# 02_battery_powered_v0001.net
KiCad netlist of a schematic drawn in EAGLE
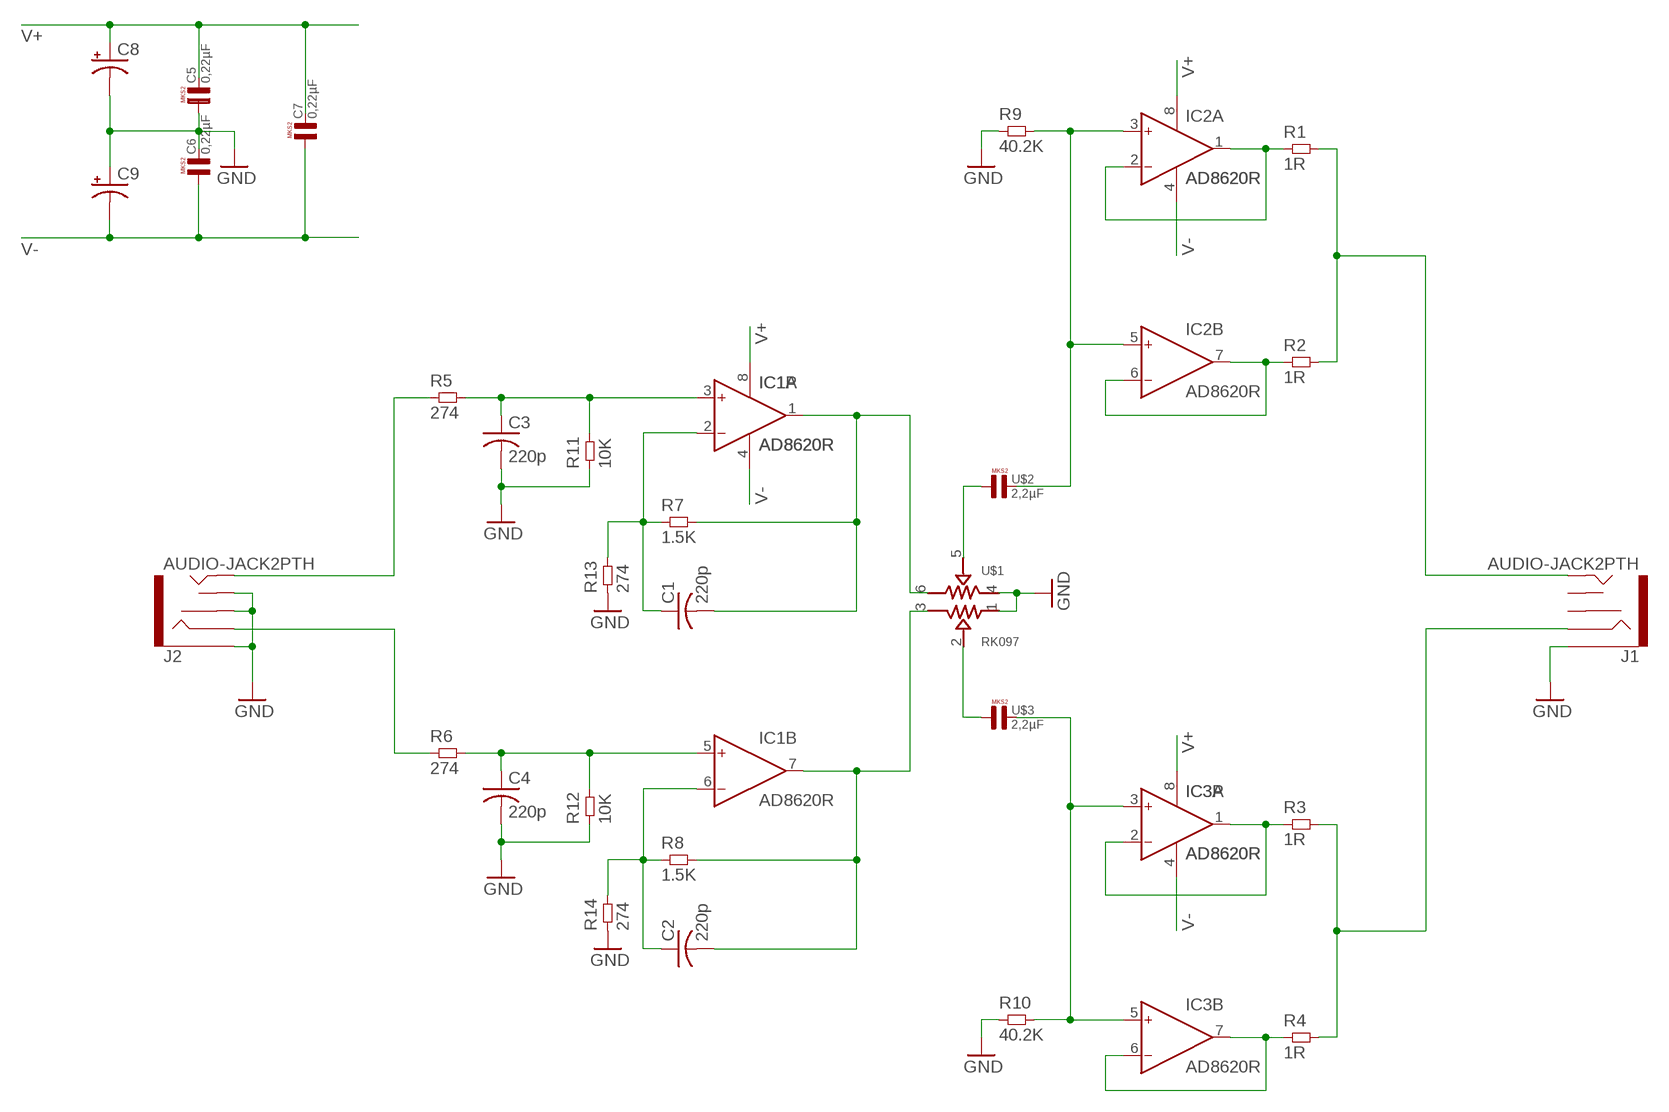
[diagram p0: schematic, sheet 1]

(export (version "E")
  (design (tool "Eeschema 10.0.6"))
  (components
    (comp (ref "C1")
      (value "220p")
      (footprint "eagle-import:C025-050X050")
      (libsource (lib "eagle-import") (part "C-US025-050X050"))
    )
    (comp (ref "C2")
      (value "220p")
      (footprint "eagle-import:C025-050X050")
      (libsource (lib "eagle-import") (part "C-US025-050X050"))
    )
    (comp (ref "C3")
      (value "220p")
      (footprint "eagle-import:C025-050X050")
      (libsource (lib "eagle-import") (part "C-US025-050X050"))
    )
    (comp (ref "C4")
      (value "220p")
      (footprint "eagle-import:C025-050X050")
      (libsource (lib "eagle-import") (part "C-US025-050X050"))
    )
    (comp (ref "C5")
      (value "0,22µF")
      (footprint "eagle-import:R5B3")
      (libsource (lib "eagle-import") (part "0,22µF"))
    )
    (comp (ref "C6")
      (value "0,22µF")
      (footprint "eagle-import:R5B3")
      (libsource (lib "eagle-import") (part "0,22µF"))
    )
    (comp (ref "C7")
      (value "0,22µF")
      (footprint "eagle-import:R5B3")
      (libsource (lib "eagle-import") (part "0,22µF"))
    )
    (comp (ref "C8")
      (value "CPOL-US150CLZ-1010")
      (footprint "eagle-import:150CLZ-1010")
      (libsource (lib "eagle-import") (part "CPOL-US150CLZ-1010"))
    )
    (comp (ref "C9")
      (value "CPOL-US150CLZ-1010")
      (footprint "eagle-import:150CLZ-1010")
      (libsource (lib "eagle-import") (part "CPOL-US150CLZ-1010"))
    )
    (comp (ref "IC1")
      (value "AD8620R")
      (footprint "eagle-import:SO8")
      (fields (field (name "MF") "ALTERA CORPORATION") (field (name "MPN") "AD8620ARZ"))
      (libsource (lib "eagle-import") (part "AD8620R"))
    )
    (comp (ref "IC2")
      (value "AD8620R")
      (footprint "eagle-import:SO8")
      (fields (field (name "MF") "ALTERA CORPORATION") (field (name "MPN") "AD8620ARZ"))
      (libsource (lib "eagle-import") (part "AD8620R"))
    )
    (comp (ref "IC3")
      (value "AD8620R")
      (footprint "eagle-import:SO8")
      (fields (field (name "MF") "ALTERA CORPORATION") (field (name "MPN") "AD8620ARZ"))
      (libsource (lib "eagle-import") (part "AD8620R"))
    )
    (comp (ref "J1")
      (value "AUDIO-JACK2PTH")
      (footprint "eagle-import:AUDIO-JACK")
      (libsource (lib "eagle-import") (part "AUDIO-JACK2PTH"))
    )
    (comp (ref "J2")
      (value "AUDIO-JACK2PTH")
      (footprint "eagle-import:AUDIO-JACK")
      (libsource (lib "eagle-import") (part "AUDIO-JACK2PTH"))
    )
    (comp (ref "R1")
      (value "1R")
      (footprint "eagle-import:1206L3")
      (libsource (lib "eagle-import") (part "RES1206L3"))
    )
    (comp (ref "R2")
      (value "1R")
      (footprint "eagle-import:1206L3")
      (libsource (lib "eagle-import") (part "RES1206L3"))
    )
    (comp (ref "R3")
      (value "1R")
      (footprint "eagle-import:1206L3")
      (libsource (lib "eagle-import") (part "RES1206L3"))
    )
    (comp (ref "R4")
      (value "1R")
      (footprint "eagle-import:1206L3")
      (libsource (lib "eagle-import") (part "RES1206L3"))
    )
    (comp (ref "R5")
      (value "274")
      (footprint "eagle-import:0603L3")
      (libsource (lib "eagle-import") (part "RES0603L3"))
    )
    (comp (ref "R6")
      (value "274")
      (footprint "eagle-import:0603L3")
      (libsource (lib "eagle-import") (part "RES0603L3"))
    )
    (comp (ref "R7")
      (value "1.5K")
      (footprint "eagle-import:0603L3")
      (libsource (lib "eagle-import") (part "RES0603L3"))
    )
    (comp (ref "R8")
      (value "1.5K")
      (footprint "eagle-import:0603L3")
      (libsource (lib "eagle-import") (part "RES0603L3"))
    )
    (comp (ref "R9")
      (value "40.2K")
      (footprint "eagle-import:0603L3")
      (libsource (lib "eagle-import") (part "RES0603L3"))
    )
    (comp (ref "R10")
      (value "40.2K")
      (footprint "eagle-import:0603L3")
      (libsource (lib "eagle-import") (part "RES0603L3"))
    )
    (comp (ref "R11")
      (value "10K")
      (footprint "eagle-import:0603L3")
      (libsource (lib "eagle-import") (part "RES0603L3"))
    )
    (comp (ref "R12")
      (value "10K")
      (footprint "eagle-import:0603L3")
      (libsource (lib "eagle-import") (part "RES0603L3"))
    )
    (comp (ref "R13")
      (value "274")
      (footprint "eagle-import:0603L3")
      (libsource (lib "eagle-import") (part "RES0603L3"))
    )
    (comp (ref "R14")
      (value "274")
      (footprint "eagle-import:0603L3")
      (libsource (lib "eagle-import") (part "RES0603L3"))
    )
    (comp (ref "U$1")
      (value "RK097")
      (footprint "eagle-import:RK097")
      (libsource (lib "eagle-import") (part "RK097"))
    )
    (comp (ref "U$2")
      (value "2,2µF")
      (footprint "eagle-import:R5B7K2")
      (libsource (lib "eagle-import") (part "2,2µF"))
    )
    (comp (ref "U$3")
      (value "2,2µF")
      (footprint "eagle-import:R5B7K2")
      (libsource (lib "eagle-import") (part "2,2µF"))
    )
  )
  (nets
    (net (code "1") (name "/V+") (class "Default")
      (node (ref "C5") (pin "2") (pinfunction "2_2") (pintype "passive"))
      (node (ref "C7") (pin "2") (pinfunction "2_2") (pintype "passive"))
      (node (ref "C8") (pin "+") (pinfunction "+_+") (pintype "passive"))
      (node (ref "IC1") (pin "8") (pinfunction "V+_8") (pintype "power_in"))
      (node (ref "IC2") (pin "8") (pinfunction "V+_8") (pintype "power_in"))
      (node (ref "IC3") (pin "8") (pinfunction "V+_8") (pintype "power_in"))
    )
    (net (code "2") (name "/V-") (class "Default")
      (node (ref "C6") (pin "1") (pinfunction "1_1") (pintype "passive"))
      (node (ref "C7") (pin "1") (pinfunction "1_1") (pintype "passive"))
      (node (ref "C9") (pin "-") (pinfunction "-_-") (pintype "passive"))
      (node (ref "IC1") (pin "4") (pinfunction "V-_4") (pintype "power_in"))
      (node (ref "IC2") (pin "4") (pinfunction "V-_4") (pintype "power_in"))
      (node (ref "IC3") (pin "4") (pinfunction "V-_4") (pintype "power_in"))
    )
    (net (code "3") (name "GND") (class "Default")
      (node (ref "C3") (pin "2") (pinfunction "2_2") (pintype "passive"))
      (node (ref "C4") (pin "2") (pinfunction "2_2") (pintype "passive"))
      (node (ref "C5") (pin "1") (pinfunction "1_1") (pintype "passive"))
      (node (ref "C6") (pin "2") (pinfunction "2_2") (pintype "passive"))
      (node (ref "C8") (pin "-") (pinfunction "-_-") (pintype "passive"))
      (node (ref "C9") (pin "+") (pinfunction "+_+") (pintype "passive"))
      (node (ref "J1") (pin "SLEEVE") (pinfunction "SLEEVE_SLEEVE") (pintype "bidirectional"))
      (node (ref "J2") (pin "RSH") (pinfunction "RSH_RSH") (pintype "bidirectional"))
      (node (ref "J2") (pin "SLEEVE") (pinfunction "SLEEVE_SLEEVE") (pintype "bidirectional"))
      (node (ref "J2") (pin "TSH") (pinfunction "TSH_TSH") (pintype "bidirectional"))
      (node (ref "R10") (pin "P$1") (pinfunction "1_P$1") (pintype "bidirectional"))
      (node (ref "R11") (pin "P$1") (pinfunction "1_P$1") (pintype "bidirectional"))
      (node (ref "R12") (pin "P$1") (pinfunction "1_P$1") (pintype "bidirectional"))
      (node (ref "R13") (pin "P$1") (pinfunction "1_P$1") (pintype "bidirectional"))
      (node (ref "R14") (pin "P$1") (pinfunction "1_P$1") (pintype "bidirectional"))
      (node (ref "R9") (pin "P$1") (pinfunction "1_P$1") (pintype "bidirectional"))
      (node (ref "U$1") (pin "1") (pinfunction "1_1") (pintype "bidirectional"))
      (node (ref "U$1") (pin "4") (pinfunction "4_4") (pintype "bidirectional"))
    )
    (net (code "4") (name "Net-(IC1A-IN+)") (class "Default")
      (node (ref "C3") (pin "1") (pinfunction "1_1") (pintype "passive"))
      (node (ref "IC1") (pin "3") (pinfunction "IN+_3") (pintype "input"))
      (node (ref "R11") (pin "P$2") (pinfunction "2_P$2") (pintype "bidirectional"))
      (node (ref "R5") (pin "P$2") (pinfunction "2_P$2") (pintype "bidirectional"))
    )
    (net (code "5") (name "Net-(IC1A-IN-)") (class "Default")
      (node (ref "C1") (pin "1") (pinfunction "1_1") (pintype "passive"))
      (node (ref "IC1") (pin "2") (pinfunction "IN-_2") (pintype "input"))
      (node (ref "R13") (pin "P$2") (pinfunction "2_P$2") (pintype "bidirectional"))
      (node (ref "R7") (pin "P$1") (pinfunction "1_P$1") (pintype "bidirectional"))
    )
    (net (code "6") (name "Net-(IC1A-OUT)") (class "Default")
      (node (ref "C1") (pin "2") (pinfunction "2_2") (pintype "passive"))
      (node (ref "IC1") (pin "1") (pinfunction "OUT_1") (pintype "output"))
      (node (ref "R7") (pin "P$2") (pinfunction "2_P$2") (pintype "bidirectional"))
      (node (ref "U$1") (pin "6") (pinfunction "6_6") (pintype "bidirectional"))
    )
    (net (code "7") (name "Net-(IC1B-IN+)") (class "Default")
      (node (ref "C4") (pin "1") (pinfunction "1_1") (pintype "passive"))
      (node (ref "IC1") (pin "5") (pinfunction "IN+_5") (pintype "input"))
      (node (ref "R12") (pin "P$2") (pinfunction "2_P$2") (pintype "bidirectional"))
      (node (ref "R6") (pin "P$2") (pinfunction "2_P$2") (pintype "bidirectional"))
    )
    (net (code "8") (name "Net-(IC1B-IN-)") (class "Default")
      (node (ref "C2") (pin "1") (pinfunction "1_1") (pintype "passive"))
      (node (ref "IC1") (pin "6") (pinfunction "IN-_6") (pintype "input"))
      (node (ref "R14") (pin "P$2") (pinfunction "2_P$2") (pintype "bidirectional"))
      (node (ref "R8") (pin "P$1") (pinfunction "1_P$1") (pintype "bidirectional"))
    )
    (net (code "9") (name "Net-(IC1B-OUT)") (class "Default")
      (node (ref "C2") (pin "2") (pinfunction "2_2") (pintype "passive"))
      (node (ref "IC1") (pin "7") (pinfunction "OUT_7") (pintype "output"))
      (node (ref "R8") (pin "P$2") (pinfunction "2_P$2") (pintype "bidirectional"))
      (node (ref "U$1") (pin "3") (pinfunction "3_3") (pintype "bidirectional"))
    )
    (net (code "10") (name "Net-(IC2A-IN+)") (class "Default")
      (node (ref "IC2") (pin "3") (pinfunction "IN+_3") (pintype "input"))
      (node (ref "IC2") (pin "5") (pinfunction "IN+_5") (pintype "input"))
      (node (ref "R9") (pin "P$2") (pinfunction "2_P$2") (pintype "bidirectional"))
      (node (ref "U$2") (pin "2") (pinfunction "2_2") (pintype "passive"))
    )
    (net (code "11") (name "Net-(IC2A-IN-)") (class "Default")
      (node (ref "IC2") (pin "1") (pinfunction "OUT_1") (pintype "output"))
      (node (ref "IC2") (pin "2") (pinfunction "IN-_2") (pintype "input"))
      (node (ref "R1") (pin "1") (pinfunction "1_1") (pintype "bidirectional"))
    )
    (net (code "12") (name "Net-(IC2B-IN-)") (class "Default")
      (node (ref "IC2") (pin "6") (pinfunction "IN-_6") (pintype "input"))
      (node (ref "IC2") (pin "7") (pinfunction "OUT_7") (pintype "output"))
      (node (ref "R2") (pin "1") (pinfunction "1_1") (pintype "bidirectional"))
    )
    (net (code "13") (name "Net-(IC3A-IN+)") (class "Default")
      (node (ref "IC3") (pin "3") (pinfunction "IN+_3") (pintype "input"))
      (node (ref "IC3") (pin "5") (pinfunction "IN+_5") (pintype "input"))
      (node (ref "R10") (pin "P$2") (pinfunction "2_P$2") (pintype "bidirectional"))
      (node (ref "U$3") (pin "2") (pinfunction "2_2") (pintype "passive"))
    )
    (net (code "14") (name "Net-(IC3A-IN-)") (class "Default")
      (node (ref "IC3") (pin "1") (pinfunction "OUT_1") (pintype "output"))
      (node (ref "IC3") (pin "2") (pinfunction "IN-_2") (pintype "input"))
      (node (ref "R3") (pin "1") (pinfunction "1_1") (pintype "bidirectional"))
    )
    (net (code "15") (name "Net-(IC3B-IN-)") (class "Default")
      (node (ref "IC3") (pin "6") (pinfunction "IN-_6") (pintype "input"))
      (node (ref "IC3") (pin "7") (pinfunction "OUT_7") (pintype "output"))
      (node (ref "R4") (pin "1") (pinfunction "1_1") (pintype "bidirectional"))
    )
    (net (code "16") (name "Net-(J1-PadRING)") (class "Default")
      (node (ref "J1") (pin "RING") (pinfunction "RING_RING") (pintype "bidirectional"))
      (node (ref "R3") (pin "2") (pinfunction "2_2") (pintype "bidirectional"))
      (node (ref "R4") (pin "2") (pinfunction "2_2") (pintype "bidirectional"))
    )
    (net (code "17") (name "Net-(J1-PadTIP)") (class "Default")
      (node (ref "J1") (pin "TIP") (pinfunction "TIP_TIP") (pintype "bidirectional"))
      (node (ref "R1") (pin "2") (pinfunction "2_2") (pintype "bidirectional"))
      (node (ref "R2") (pin "2") (pinfunction "2_2") (pintype "bidirectional"))
    )
    (net (code "18") (name "Net-(R5-1)") (class "Default")
      (node (ref "J2") (pin "TIP") (pinfunction "TIP_TIP") (pintype "bidirectional"))
      (node (ref "R5") (pin "P$1") (pinfunction "1_P$1") (pintype "bidirectional"))
    )
    (net (code "19") (name "Net-(R6-1)") (class "Default")
      (node (ref "J2") (pin "RING") (pinfunction "RING_RING") (pintype "bidirectional"))
      (node (ref "R6") (pin "P$1") (pinfunction "1_P$1") (pintype "bidirectional"))
    )
    (net (code "20") (name "Net-(U$1-Pad2)") (class "Default")
      (node (ref "U$1") (pin "2") (pinfunction "2_2") (pintype "bidirectional"))
      (node (ref "U$3") (pin "1") (pinfunction "1_1") (pintype "passive"))
    )
    (net (code "21") (name "Net-(U$1-Pad5)") (class "Default")
      (node (ref "U$1") (pin "5") (pinfunction "5_5") (pintype "bidirectional"))
      (node (ref "U$2") (pin "1") (pinfunction "1_1") (pintype "passive"))
    )
    (net (code "22") (name "unconnected-(J1-PadRSH)") (class "Default")
      (node (ref "J1") (pin "RSH") (pinfunction "RSH_RSH") (pintype "bidirectional"))
    )
    (net (code "23") (name "unconnected-(J1-PadTSH)") (class "Default")
      (node (ref "J1") (pin "TSH") (pinfunction "TSH_TSH") (pintype "bidirectional"))
    )
  )
)
